# FDL-2_DCP.net
KiCad netlist of a schematic drawn in EAGLE
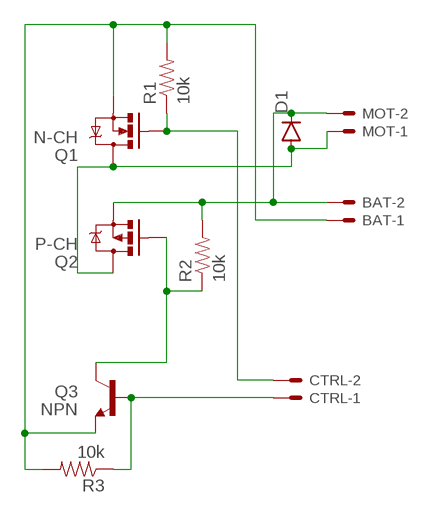
[diagram p0: schematic, sheet 1]

(export (version "E")
  (design (tool "Eeschema 10.0.6"))
  (components
    (comp (ref "BAT")
      (value "JST-XH-02-PIN-LONG-PAD")
      (footprint "eagle-import:JST-XH-02-PACKAGE-LONG-PAD")
      (libsource (lib "eagle-import") (part "JST-XH-02-PIN-LONG-PAD"))
    )
    (comp (ref "CTRL")
      (value "JST-XH-02-PIN-LONG-PAD")
      (footprint "eagle-import:JST-XH-02-PACKAGE-LONG-PAD")
      (libsource (lib "eagle-import") (part "JST-XH-02-PIN-LONG-PAD"))
    )
    (comp (ref "D1")
      (value "DIODEPTH")
      (footprint "eagle-import:DIODE-1N4001")
      (libsource (lib "eagle-import") (part "DIODEPTH"))
    )
    (comp (ref "MOT")
      (value "JST-XH-02-PIN-LONG-PAD")
      (footprint "eagle-import:JST-XH-02-PACKAGE-LONG-PAD")
      (libsource (lib "eagle-import") (part "JST-XH-02-PIN-LONG-PAD"))
    )
    (comp (ref "Q1")
      (value "N-CH")
      (footprint "eagle-import:TO220V")
      (libsource (lib "eagle-import") (part "MOSFET-NCHANNELFQP30N06L"))
    )
    (comp (ref "Q2")
      (value "P-CH")
      (footprint "eagle-import:TO220V")
      (libsource (lib "eagle-import") (part "MOSFET-PCHANNELNDP6020P_20V_24A_LOW_VGS_TH"))
    )
    (comp (ref "Q3")
      (value "NPN")
      (footprint "eagle-import:TO-92")
      (libsource (lib "eagle-import") (part "TRANSISTOR_NPN2N3904"))
    )
    (comp (ref "R1")
      (value "10k")
      (footprint "eagle-import:AXIAL-0.3EZ")
      (libsource (lib "eagle-import") (part "10KOHM-1/4W-1%(PTH)HORIZ-KIT"))
    )
    (comp (ref "R2")
      (value "10k")
      (footprint "eagle-import:AXIAL-0.3EZ")
      (libsource (lib "eagle-import") (part "10KOHM-1/4W-1%(PTH)HORIZ-KIT"))
    )
    (comp (ref "R3")
      (value "10k")
      (footprint "eagle-import:AXIAL-0.3EZ")
      (libsource (lib "eagle-import") (part "10KOHM-1/4W-1%(PTH)HORIZ-KIT"))
    )
  )
  (nets
    (net (code "1") (name "Net-(BATA-S)") (class "Default")
      (node (ref "BAT") (pin "1") (pinfunction "S_1") (pintype "passive"))
      (node (ref "Q1") (pin "3") (pinfunction "S_3") (pintype "passive"))
      (node (ref "Q3") (pin "1") (pinfunction "E_1") (pintype "passive"))
      (node (ref "R1") (pin "P$2") (pinfunction "2_P$2") (pintype "passive"))
      (node (ref "R3") (pin "P$2") (pinfunction "2_P$2") (pintype "passive"))
    )
    (net (code "2") (name "Net-(BATB-S)") (class "Default")
      (node (ref "BAT") (pin "2") (pinfunction "S_2") (pintype "passive"))
      (node (ref "D1") (pin "C") (pinfunction "C_C") (pintype "passive"))
      (node (ref "MOT") (pin "2") (pinfunction "S_2") (pintype "passive"))
      (node (ref "Q2") (pin "3") (pinfunction "S_3") (pintype "passive"))
      (node (ref "R2") (pin "P$2") (pinfunction "2_P$2") (pintype "passive"))
    )
    (net (code "3") (name "Net-(CTRLA-S)") (class "Default")
      (node (ref "CTRL") (pin "1") (pinfunction "S_1") (pintype "passive"))
      (node (ref "Q3") (pin "2") (pinfunction "B_2") (pintype "passive"))
      (node (ref "R3") (pin "P$1") (pinfunction "1_P$1") (pintype "passive"))
    )
    (net (code "4") (name "Net-(CTRLB-S)") (class "Default")
      (node (ref "CTRL") (pin "2") (pinfunction "S_2") (pintype "passive"))
      (node (ref "Q1") (pin "1") (pinfunction "G_1") (pintype "passive"))
      (node (ref "R1") (pin "P$1") (pinfunction "1_P$1") (pintype "passive"))
    )
    (net (code "5") (name "Net-(MOTA-S)") (class "Default")
      (node (ref "D1") (pin "A") (pinfunction "A_A") (pintype "passive"))
      (node (ref "MOT") (pin "1") (pinfunction "S_1") (pintype "passive"))
      (node (ref "Q1") (pin "2") (pinfunction "D_2") (pintype "passive"))
      (node (ref "Q2") (pin "2") (pinfunction "D_2") (pintype "passive"))
    )
    (net (code "6") (name "Net-(Q2-G)") (class "Default")
      (node (ref "Q2") (pin "1") (pinfunction "G_1") (pintype "passive"))
      (node (ref "Q3") (pin "3") (pinfunction "C_3") (pintype "passive"))
      (node (ref "R2") (pin "P$1") (pinfunction "1_P$1") (pintype "passive"))
    )
  )
)
